# CAN-Sheet.net
KiCad netlist of a schematic drawn in Altium Designer
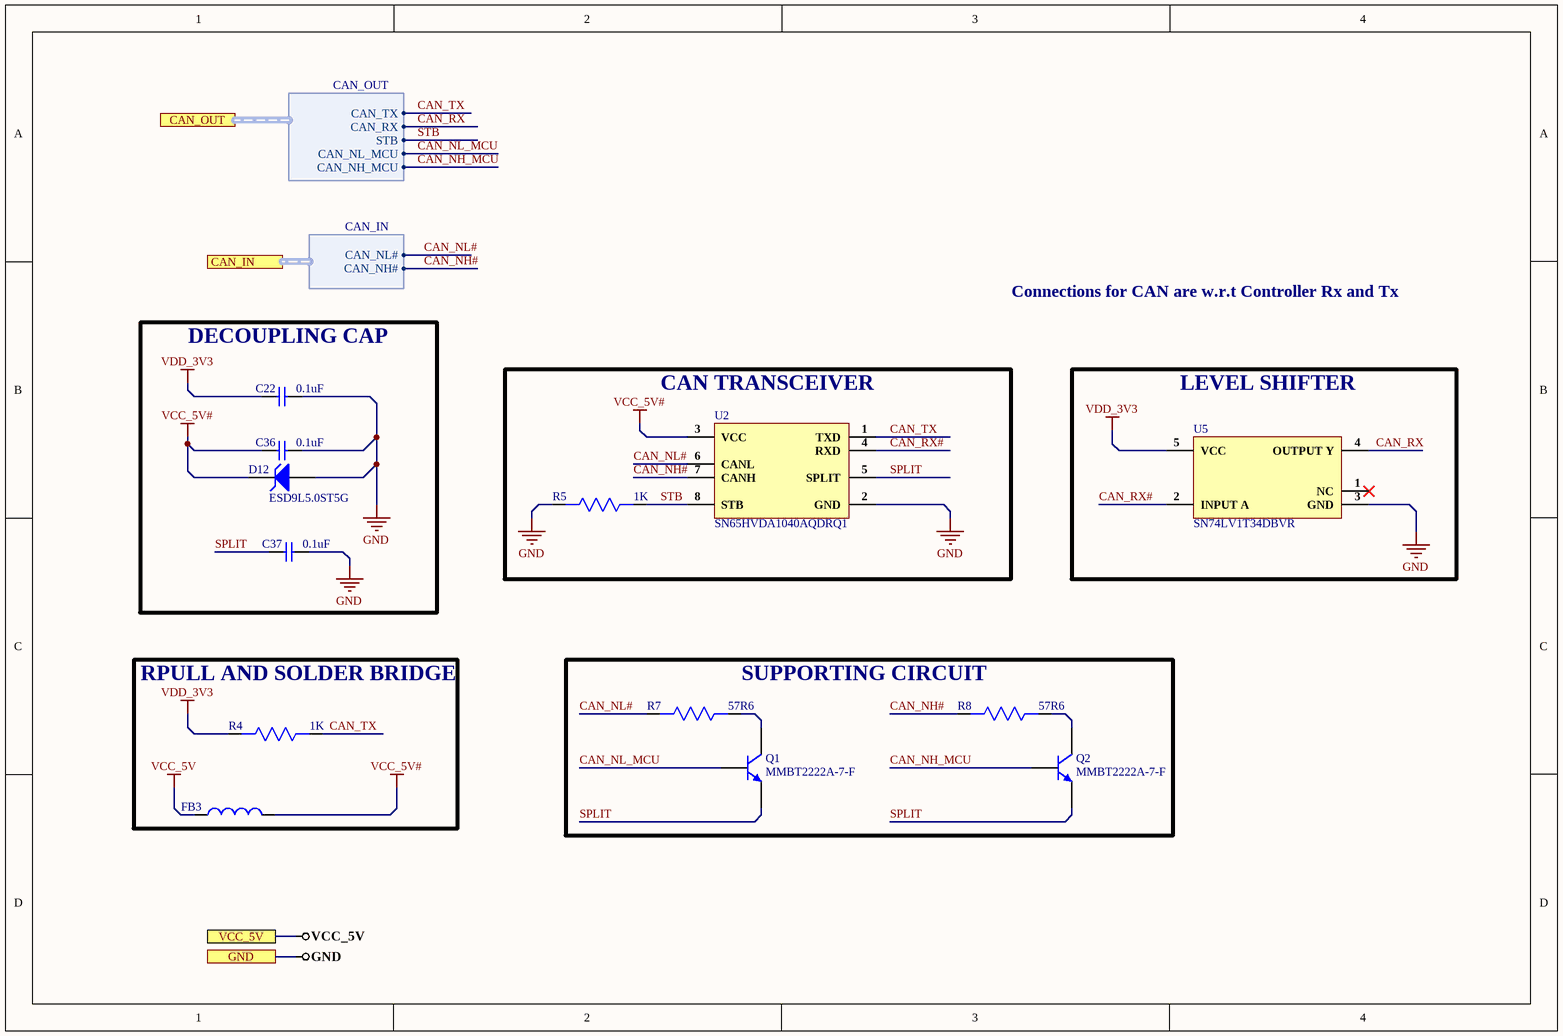
[diagram p0: CAN-Sheet.SchDoc]

(export (version "E")
  (design (tool "Eeschema 10.0.6"))
  (components
    (comp (ref "C22")
      (value "0.1uF")
      (footprint "Cap 0603")
      (description "Cap Ceramic 0.1uF 50VDC X7R 10% SMD 0603 Paper T/R")
      (fields
        (field (name "MANUFACTURER") "Samsung")
        (field (name "MANUFACTURER PART NUMBER") "CL10B104KB8NNNC")
      )
      (libsource (lib "Cole_Benson") (part "CL10B104KB8NNNC"))
    )
    (comp (ref "C36")
      (value "0.1uF")
      (footprint "Cap0603")
      (description "Cap Ceramic 0.1uF 50VDC X7R 10% SMD 0603 Paper T/R")
      (fields
        (field (name "MANUFACTURER") "Samsung")
        (field (name "MANUFACTURER PART NUMBER") "CL10B104KB8NNNC")
      )
      (libsource (lib "Cole_Benson") (part "CL10B104KB8NNNC"))
    )
    (comp (ref "C37")
      (value "0.1uF")
      (footprint "Cap0603")
      (description "Cap Ceramic 0.1uF 50VDC X7R 10% SMD 0603 Paper T/R")
      (fields
        (field (name "MANUFACTURER") "Samsung")
        (field (name "MANUFACTURER PART NUMBER") "CL10B104KB8NNNC")
      )
      (libsource (lib "Cole_Benson") (part "CL10B104KB8NNNC"))
    )
    (comp (ref "D12")
      (value "ESD9L5.0ST5G")
      (footprint "SOD-923")
      (description "TVS DIODE 5V 9.8V SOD923")
      (fields (field (name "MANUFACTURER") "ON Semiconductor"))
      (libsource (lib "Cole_Benson") (part "ESD9L5.0ST5G"))
    )
    (comp (ref "FB3")
      (value "MPZ1608S121ATDH5")
      (footprint "MPZ1608S121ATDH5")
      (description "Ferrite Beads Multi-Layer 120Ohm 25% 100MHz 2A 45mOhm DCR 0603 Automotive T/R")
      (fields (field (name "MANUFACTURER") "TDK") (field (name "TOLERANCE") "25%"))
      (libsource (lib "Cole_Benson") (part "MPZ1608S121ATDH5"))
    )
    (comp (ref "Q1")
      (value "MMBT2222A-7-F")
      (footprint "SOT-23")
      (description "TRANS NPN 40V 0.6A SMD SOT23-3")
      (fields (field (name "MANUFACTURER") "Diodes") (field (name "VOLTAGE") "40V"))
      (libsource (lib "Cole_Benson") (part "MMBT2222A-7-F"))
    )
    (comp (ref "Q2")
      (value "MMBT2222A-7-F")
      (footprint "SOT-23")
      (description "TRANS NPN 40V 0.6A SMD SOT23-3")
      (fields (field (name "MANUFACTURER") "Diodes") (field (name "VOLTAGE") "40V"))
      (libsource (lib "Cole_Benson") (part "MMBT2222A-7-F"))
    )
    (comp (ref "R4")
      (value "1K")
      (footprint "Res0603")
      (description "RES SMD 1K 0.1W 0603  75 V, Thick Film")
      (fields
        (field (name "MANUFACTURER") "Yageo")
        (field (name "MANUFACTURER PART NUMBER") "RC0603JR-071KL")
      )
      (libsource (lib "Cole_Benson") (part "RC0603JR-071KL"))
    )
    (comp (ref "R5")
      (value "1K")
      (footprint "Res0603")
      (description "RES SMD 1K 0.1W 0603  75 V, Thick Film")
      (fields
        (field (name "MANUFACTURER") "Yageo")
        (field (name "MANUFACTURER PART NUMBER") "RC0603JR-071KL")
      )
      (libsource (lib "Cole_Benson") (part "RC0603JR-071KL"))
    )
    (comp (ref "R7")
      (value "57R6")
      (footprint "Res0603")
      (description "RES SMD 57.6 OHM 1% 1/10W 0603")
      (fields
        (field (name "MANUFACTURER") "Yageo")
        (field (name "MANUFACTURER PART NUMBER") "RC0603FR-0757R6L")
      )
      (libsource (lib "Cole_Benson") (part "RC0603FR-0757R6L"))
    )
    (comp (ref "R8")
      (value "57R6")
      (footprint "Res0603")
      (description "RES SMD 57.6 OHM 1% 1/10W 0603")
      (fields
        (field (name "MANUFACTURER") "Yageo")
        (field (name "MANUFACTURER PART NUMBER") "RC0603FR-0757R6L")
      )
      (libsource (lib "Cole_Benson") (part "RC0603FR-0757R6L"))
    )
    (comp (ref "U2")
      (value "SN65HVDA1040AQDRQ1")
      (footprint "SOIC-8")
      (description "IC TRANSCEIVER HALF 1/1 8SOIC")
      (fields (field (name "MANUFACTURER") "Texas Instruments"))
      (libsource (lib "Cole_Benson") (part "SN65HVDA1040AQDRQ1"))
    )
    (comp (ref "U5")
      (value "SN74LV1T34DBVR")
      (footprint "SOT-23-5")
      (description "IC BUF NON-INVERT 5.5V SOT23-5")
      (fields (field (name "MANUFACTURER") "Texas Instruments"))
      (libsource (lib "Cole_Benson") (part "SN74LV1T34DBVR"))
    )
  )
  (nets
    (net (code "3") (name "/CAN_NH#") (class "Default")
      (node (ref "R8") (pin "2") (pintype "passive"))
      (node (ref "U2") (pin "7") (pinfunction "CANH_7") (pintype "passive"))
    )
    (net (code "4") (name "/CAN_NH_MCU") (class "Default")
      (node (ref "Q2") (pin "1") (pinfunction "B_1") (pintype "passive"))
    )
    (net (code "5") (name "/CAN_NL#") (class "Default")
      (node (ref "R7") (pin "2") (pintype "passive"))
      (node (ref "U2") (pin "6") (pinfunction "CANL_6") (pintype "passive"))
    )
    (net (code "6") (name "/CAN_NL_MCU") (class "Default")
      (node (ref "Q1") (pin "1") (pinfunction "B_1") (pintype "passive"))
    )
    (net (code "7") (name "/CAN_RX") (class "Default")
      (node (ref "U5") (pin "4") (pinfunction "OUTPUT_Y_4") (pintype "passive"))
    )
    (net (code "8") (name "/CAN_RX#") (class "Default")
      (node (ref "U2") (pin "4") (pinfunction "RXD_4") (pintype "passive"))
      (node (ref "U5") (pin "2") (pinfunction "INPUT_A_2") (pintype "passive"))
    )
    (net (code "9") (name "/CAN_TX") (class "Default")
      (node (ref "R4") (pin "1") (pintype "passive"))
      (node (ref "U2") (pin "1") (pinfunction "TXD_1") (pintype "passive"))
    )
    (net (code "10") (name "/SPLIT") (class "Default")
      (node (ref "C37") (pin "1") (pinfunction "1_1") (pintype "passive"))
      (node (ref "Q1") (pin "2") (pinfunction "E_2") (pintype "passive"))
      (node (ref "Q2") (pin "2") (pinfunction "E_2") (pintype "passive"))
      (node (ref "U2") (pin "5") (pinfunction "SPLIT_5") (pintype "passive"))
    )
    (net (code "11") (name "/STB") (class "Default")
      (node (ref "R5") (pin "1") (pintype "passive"))
      (node (ref "U2") (pin "8") (pinfunction "STB_8") (pintype "passive"))
    )
    (net (code "14") (name "GND") (class "Default")
      (node (ref "C22") (pin "2") (pinfunction "2_2") (pintype "passive"))
      (node (ref "C36") (pin "2") (pinfunction "2_2") (pintype "passive"))
      (node (ref "C37") (pin "2") (pinfunction "2_2") (pintype "passive"))
      (node (ref "D12") (pin "2") (pinfunction "A_2") (pintype "passive"))
      (node (ref "R5") (pin "2") (pintype "passive"))
      (node (ref "U2") (pin "2") (pinfunction "GND_2") (pintype "passive"))
      (node (ref "U5") (pin "3") (pinfunction "GND_3") (pintype "passive"))
    )
    (net (code "15") (name "Net-(Q1-C)") (class "Default")
      (node (ref "Q1") (pin "3") (pinfunction "C_3") (pintype "passive"))
      (node (ref "R7") (pin "1") (pintype "passive"))
    )
    (net (code "16") (name "Net-(Q2-C)") (class "Default")
      (node (ref "Q2") (pin "3") (pinfunction "C_3") (pintype "passive"))
      (node (ref "R8") (pin "1") (pintype "passive"))
    )
    (net (code "17") (name "VCC_5V") (class "Default")
      (node (ref "FB3") (pin "1") (pinfunction "1_1") (pintype "passive"))
    )
    (net (code "18") (name "VCC_5V#") (class "Default")
      (node (ref "C36") (pin "1") (pinfunction "1_1") (pintype "passive"))
      (node (ref "D12") (pin "1") (pinfunction "K_1") (pintype "passive"))
      (node (ref "FB3") (pin "2") (pinfunction "2_2") (pintype "passive"))
      (node (ref "U2") (pin "3") (pinfunction "VCC_3") (pintype "passive"))
    )
    (net (code "19") (name "VDD_3V3") (class "Default")
      (node (ref "C22") (pin "1") (pinfunction "1_1") (pintype "passive"))
      (node (ref "R4") (pin "2") (pintype "passive"))
      (node (ref "U5") (pin "5") (pinfunction "VCC_5") (pintype "passive"))
    )
    (net (code "20") (name "unconnected-(U5-NC-Pad1)") (class "Default")
      (node (ref "U5") (pin "1") (pinfunction "NC_1") (pintype "passive+no_connect"))
    )
  )
)
